# Principal.net
KiCad netlist of a schematic drawn in Altium Designer
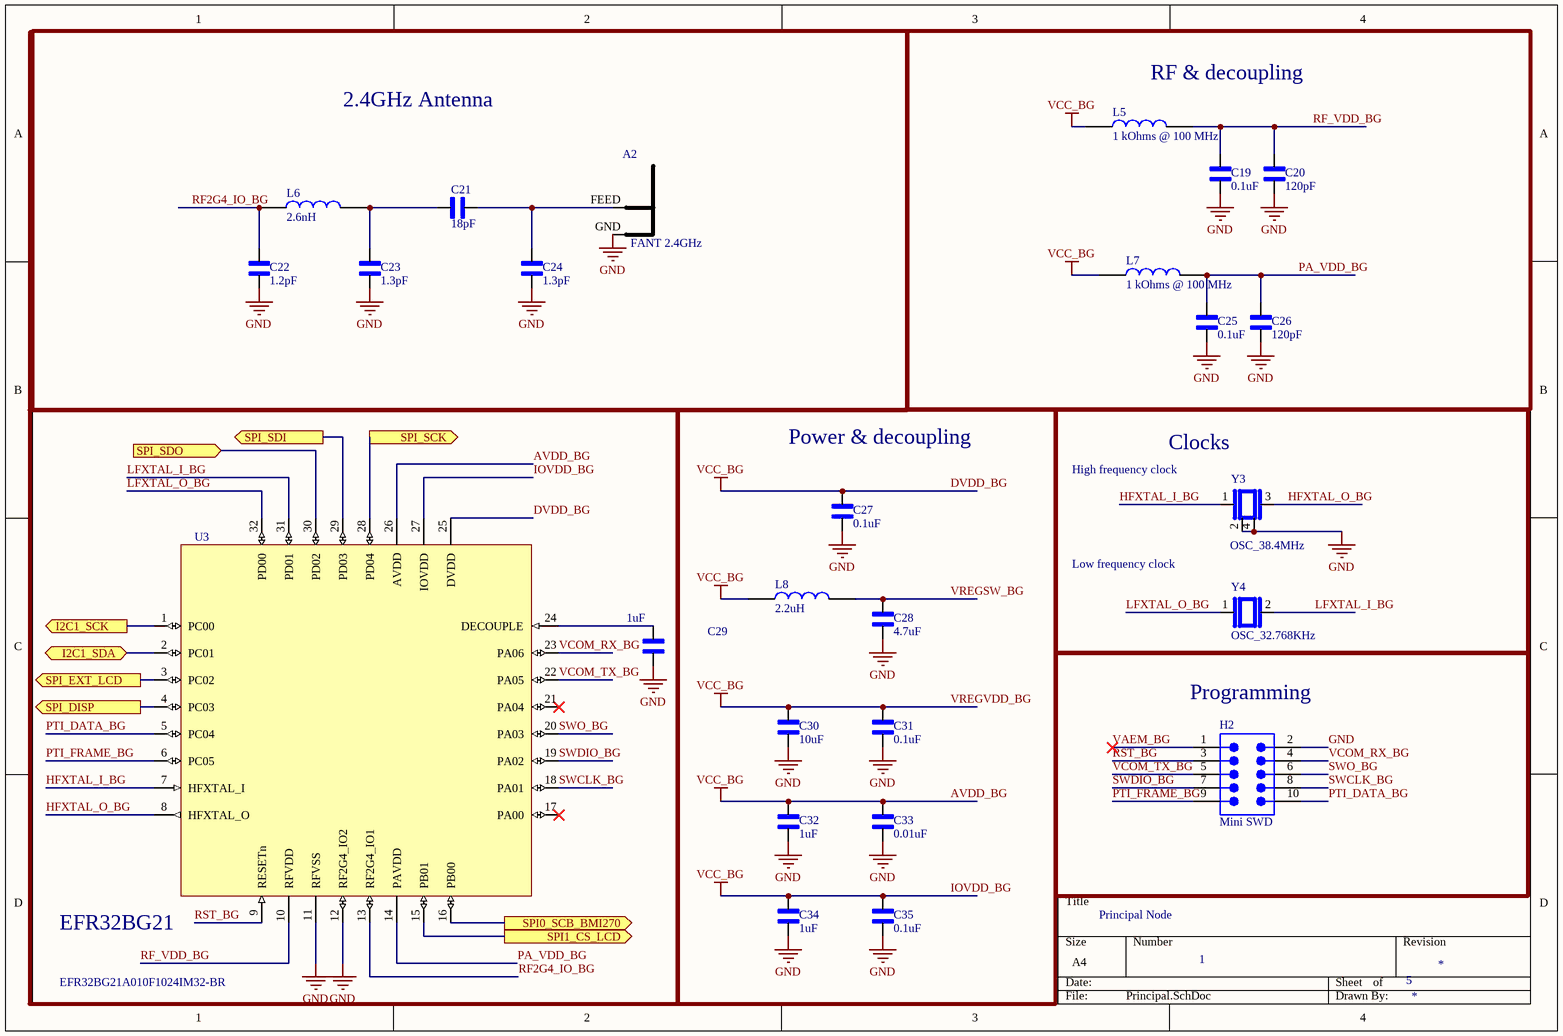
[diagram p0: Principal.SchDoc]

(export (version "E")
  (design (tool "Eeschema 10.0.6"))
  (components
    (comp (ref "A2")
      (value "FANT 2.4GHz")
      (footprint "FANT_2P4")
      (description "Inverted F antenna")
      (libsource (lib "Project_Vega") (part "FANT_2P4"))
    )
    (comp (ref "C19")
      (value "0.1uF")
      (footprint "CAPC1608X90")
      (description "0.1 ÂµF Â±10% 50V Ceramic Capacitor X7R 0603 (1608 Metric)")
      (fields (field (name "MF") "Yageo") (field (name "MP") "CC0603KRX7R9BB104"))
      (libsource (lib "Project_Vega") (part "CC0603KRX7R9BB104"))
    )
    (comp (ref "C20")
      (value "120pF")
      (footprint "CAPC1608X90")
      (description "0.1 ÂµF Â±10% 50V Ceramic Capacitor X7R 0603 (1608 Metric)")
      (fields (field (name "MF") "Yageo") (field (name "MP") "CC0603KRX7R9BB104"))
      (libsource (lib "Project_Vega") (part "CC0603KRX7R9BB104"))
    )
    (comp (ref "C21")
      (value "18pF")
      (footprint "CAPC1608X90")
      (description "0.1 ÂµF Â±10% 50V Ceramic Capacitor X7R 0603 (1608 Metric)")
      (fields (field (name "MF") "Yageo") (field (name "MP") "CC0603KRX7R9BB104"))
      (libsource (lib "") (part "CC0603KRX7R9BB104_1"))
    )
    (comp (ref "C22")
      (value "1.2pF")
      (footprint "CAPC1608X90")
      (description "0.1 ÂµF Â±10% 50V Ceramic Capacitor X7R 0603 (1608 Metric)")
      (fields (field (name "MF") "Yageo") (field (name "MP") "CC0603KRX7R9BB104"))
      (libsource (lib "Project_Vega") (part "CC0603KRX7R9BB104"))
    )
    (comp (ref "C23")
      (value "1.3pF")
      (footprint "CAPC1608X90")
      (description "0.1 ÂµF Â±10% 50V Ceramic Capacitor X7R 0603 (1608 Metric)")
      (fields (field (name "MF") "Yageo") (field (name "MP") "CC0603KRX7R9BB104"))
      (libsource (lib "Project_Vega") (part "CC0603KRX7R9BB104"))
    )
    (comp (ref "C24")
      (value "1.3pF")
      (footprint "CAPC1608X90")
      (description "0.1 ÂµF Â±10% 50V Ceramic Capacitor X7R 0603 (1608 Metric)")
      (fields (field (name "MF") "Yageo") (field (name "MP") "CC0603KRX7R9BB104"))
      (libsource (lib "Project_Vega") (part "CC0603KRX7R9BB104"))
    )
    (comp (ref "C25")
      (value "0.1uF")
      (footprint "CAPC1608X90")
      (description "0.1 ÂµF Â±10% 50V Ceramic Capacitor X7R 0603 (1608 Metric)")
      (fields (field (name "MF") "Yageo") (field (name "MP") "CC0603KRX7R9BB104"))
      (libsource (lib "Project_Vega") (part "CC0603KRX7R9BB104"))
    )
    (comp (ref "C26")
      (value "120pF")
      (footprint "CAPC1608X90")
      (description "0.1 ÂµF Â±10% 50V Ceramic Capacitor X7R 0603 (1608 Metric)")
      (fields (field (name "MF") "Yageo") (field (name "MP") "CC0603KRX7R9BB104"))
      (libsource (lib "Project_Vega") (part "CC0603KRX7R9BB104"))
    )
    (comp (ref "C27")
      (value "0.1uF")
      (footprint "CAPC1608X90")
      (description "0.1 ÂµF Â±10% 50V Ceramic Capacitor X7R 0603 (1608 Metric)")
      (fields (field (name "MF") "Yageo") (field (name "MP") "CC0603KRX7R9BB104"))
      (libsource (lib "Project_Vega") (part "CC0603KRX7R9BB104"))
    )
    (comp (ref "C28")
      (value "4.7uF")
      (footprint "CAPC1608X90")
      (description "0.1 ÂµF Â±10% 50V Ceramic Capacitor X7R 0603 (1608 Metric)")
      (fields (field (name "MF") "Yageo") (field (name "MP") "CC0603KRX7R9BB104"))
      (libsource (lib "Project_Vega") (part "CC0603KRX7R9BB104"))
    )
    (comp (ref "C29")
      (value "1uF")
      (footprint "CAPC1608X90")
      (description "0.1 ÂµF Â±10% 50V Ceramic Capacitor X7R 0603 (1608 Metric)")
      (fields (field (name "MF") "Yageo") (field (name "MP") "CC0603KRX7R9BB104"))
      (libsource (lib "Project_Vega") (part "CC0603KRX7R9BB104"))
    )
    (comp (ref "C30")
      (value "10uF")
      (footprint "CAPC1608X90")
      (description "0.1 ÂµF Â±10% 50V Ceramic Capacitor X7R 0603 (1608 Metric)")
      (fields (field (name "MF") "Yageo") (field (name "MP") "CC0603KRX7R9BB104"))
      (libsource (lib "Project_Vega") (part "CC0603KRX7R9BB104"))
    )
    (comp (ref "C31")
      (value "0.1uF")
      (footprint "CAPC1608X90")
      (description "0.1 ÂµF Â±10% 50V Ceramic Capacitor X7R 0603 (1608 Metric)")
      (fields (field (name "MF") "Yageo") (field (name "MP") "CC0603KRX7R9BB104"))
      (libsource (lib "Project_Vega") (part "CC0603KRX7R9BB104"))
    )
    (comp (ref "C32")
      (value "1uF")
      (footprint "CAPC1608X90")
      (description "0.1 ÂµF Â±10% 50V Ceramic Capacitor X7R 0603 (1608 Metric)")
      (fields (field (name "MF") "Yageo") (field (name "MP") "CC0603KRX7R9BB104"))
      (libsource (lib "Project_Vega") (part "CC0603KRX7R9BB104"))
    )
    (comp (ref "C33")
      (value "0.01uF")
      (footprint "CAPC1608X90")
      (description "0.1 ÂµF Â±10% 50V Ceramic Capacitor X7R 0603 (1608 Metric)")
      (fields (field (name "MF") "Yageo") (field (name "MP") "CC0603KRX7R9BB104"))
      (libsource (lib "Project_Vega") (part "CC0603KRX7R9BB104"))
    )
    (comp (ref "C34")
      (value "1uF")
      (footprint "CAPC1608X90")
      (description "0.1 ÂµF Â±10% 50V Ceramic Capacitor X7R 0603 (1608 Metric)")
      (fields (field (name "MF") "Yageo") (field (name "MP") "CC0603KRX7R9BB104"))
      (libsource (lib "Project_Vega") (part "CC0603KRX7R9BB104"))
    )
    (comp (ref "C35")
      (value "0.1uF")
      (footprint "CAPC1608X90")
      (description "0.1 ÂµF Â±10% 50V Ceramic Capacitor X7R 0603 (1608 Metric)")
      (fields (field (name "MF") "Yageo") (field (name "MP") "CC0603KRX7R9BB104"))
      (libsource (lib "Project_Vega") (part "CC0603KRX7R9BB104"))
    )
    (comp (ref "H2")
      (value "Mini SWD")
      (footprint "FTSH-105-01-XXX-DV-K")
      (description "Mini SWD 0.05\" Pitch Connector - 10 Pin SMT Box Header")
      (fields
        (field (name "MANUFACTURER") "Adafruit Industries")
        (field (name "MANUFACTURER PART NUMBER") "4048")
      )
      (libsource (lib "Connectors") (part "Debug Connector Mini SWD - 0.05{dblquote}"))
    )
    (comp (ref "L5")
      (value "1 kOhms @ 100 MHz")
      (footprint "INDC1608X95N")
      (description "Inductor with Inductance 10uH Tol.+/-20% Package 0603 (1608)")
      (fields (field (name "MP") "LQM18DN100M70L") (field (name "MF") "Murata Electronics"))
      (libsource (lib "Project_Vega") (part "LQM18DN100M70L"))
    )
    (comp (ref "L6")
      (value "2.6nH")
      (footprint "INDC1608X95N")
      (description "Inductor with Inductance 10uH Tol.+/-20% Package 0603 (1608)")
      (fields (field (name "MP") "LQM18DN100M70L") (field (name "MF") "Murata Electronics"))
      (libsource (lib "Project_Vega") (part "LQM18DN100M70L"))
    )
    (comp (ref "L7")
      (value "1 kOhms @ 100 MHz")
      (footprint "INDC1608X95N")
      (description "Inductor with Inductance 10uH Tol.+/-20% Package 0603 (1608)")
      (fields (field (name "MP") "LQM18DN100M70L") (field (name "MF") "Murata Electronics"))
      (libsource (lib "Project_Vega") (part "LQM18DN100M70L"))
    )
    (comp (ref "L8")
      (value "2.2uH")
      (footprint "INDC1608X95N")
      (description "Inductor with Inductance 10uH Tol.+/-20% Package 0603 (1608)")
      (fields (field (name "MP") "LQM18DN100M70L") (field (name "MF") "Murata Electronics"))
      (libsource (lib "Project_Vega") (part "LQM18DN100M70L"))
    )
    (comp (ref "U3")
      (value "EFR32BG21A010F1024IM32-BR")
      (footprint "QFN32-EFR32xG2xIM32-BR")
      (description "Blue Gecko, QFN32, 2.4G, 10dB, Bluetooth 5.1, 1024kB, 96kB(RAM), 20 GPIO")
      (fields (field (name "MANUFACTURER") "Silicon Labs"))
      (libsource (lib "Project_Vega") (part "EFR32BG21A010F1024IM32-BR"))
    )
    (comp (ref "Y3")
      (value "OSC_38.4MHz")
      (footprint "OSC_38.4MHz")
      (description "38.4 MHz ±10ppm Crystal 10pF 40 Ohms 4-SMD, No Lead")
      (fields
        (field (name "MF") "{'manufacturer': u'Murata Electronics'}")
        (field (name "MP") "XRCGB38M400F2P00R0")
      )
      (libsource (lib "Project_Vega") (part "OSC_38.4MHz"))
    )
    (comp (ref "Y4")
      (value "OSC_32.768KHz")
      (footprint "OSC_32.768KHz")
      (description "Tuning Fork Crystal 32.768kHz in 1.2 x 2.0mm package")
      (fields (field (name "MF") "Micro Crystal") (field (name "MP") "CM8V-T1A-32.768KHZ-7PF-20PPM-TA-QC"))
      (libsource (lib "Project_Vega") (part "OSC_32.768KHz"))
    )
  )
  (nets
    (net (code "1") (name "/HFXTAL_I_BG") (class "Default")
      (node (ref "U3") (pin "7") (pinfunction "HFXTAL_I_7") (pintype "input"))
      (node (ref "Y3") (pin "1") (pinfunction "1_1") (pintype "passive"))
    )
    (net (code "2") (name "/HFXTAL_O_BG") (class "Default")
      (node (ref "U3") (pin "8") (pinfunction "HFXTAL_O_8") (pintype "output"))
      (node (ref "Y3") (pin "3") (pinfunction "3_3") (pintype "passive"))
    )
    (net (code "3") (name "/I2C1_SCK") (class "Default")
      (node (ref "U3") (pin "1") (pinfunction "PC00_1") (pintype "bidirectional"))
    )
    (net (code "4") (name "/I2C1_SDA") (class "Default")
      (node (ref "U3") (pin "2") (pinfunction "PC01_2") (pintype "bidirectional"))
    )
    (net (code "5") (name "/LFXTAL_I_BG") (class "Default")
      (node (ref "U3") (pin "31") (pinfunction "PD01_31") (pintype "bidirectional"))
      (node (ref "Y4") (pin "2") (pinfunction "2_2") (pintype "passive"))
    )
    (net (code "6") (name "/LFXTAL_O_BG") (class "Default")
      (node (ref "U3") (pin "32") (pinfunction "PD00_32") (pintype "bidirectional"))
      (node (ref "Y4") (pin "1") (pinfunction "1_1") (pintype "passive"))
    )
    (net (code "7") (name "/PA_VDD_BG") (class "Default")
      (node (ref "C25") (pin "1") (pinfunction "1_1") (pintype "passive"))
      (node (ref "C26") (pin "1") (pinfunction "1_1") (pintype "passive"))
      (node (ref "L7") (pin "2") (pinfunction "2_2") (pintype "passive"))
      (node (ref "U3") (pin "14") (pinfunction "PAVDD_14") (pintype "power_in"))
    )
    (net (code "8") (name "/PTI_DATA_BG") (class "Default")
      (node (ref "H2") (pin "10") (pinfunction "10_10") (pintype "passive"))
      (node (ref "U3") (pin "5") (pinfunction "PC04_5") (pintype "bidirectional"))
    )
    (net (code "9") (name "/PTI_FRAME_BG") (class "Default")
      (node (ref "H2") (pin "9") (pinfunction "9_9") (pintype "passive"))
      (node (ref "U3") (pin "6") (pinfunction "PC05_6") (pintype "bidirectional"))
    )
    (net (code "10") (name "/RF2G4_IO_BG") (class "Default")
      (node (ref "C22") (pin "1") (pinfunction "1_1") (pintype "passive"))
      (node (ref "L6") (pin "1") (pinfunction "1_1") (pintype "passive"))
      (node (ref "U3") (pin "13") (pinfunction "RF2G4_IO1_13") (pintype "bidirectional"))
    )
    (net (code "11") (name "/RF_VDD_BG") (class "Default")
      (node (ref "C19") (pin "1") (pinfunction "1_1") (pintype "passive"))
      (node (ref "C20") (pin "1") (pinfunction "1_1") (pintype "passive"))
      (node (ref "L5") (pin "2") (pinfunction "2_2") (pintype "passive"))
      (node (ref "U3") (pin "10") (pinfunction "RFVDD_10") (pintype "power_in"))
    )
    (net (code "12") (name "/RST_BG") (class "Default")
      (node (ref "H2") (pin "3") (pinfunction "3_3") (pintype "passive"))
      (node (ref "U3") (pin "9") (pinfunction "RESETn_9") (pintype "input"))
    )
    (net (code "13") (name "/SPI0_SCB_BMI270") (class "Default")
      (node (ref "U3") (pin "16") (pinfunction "PB00_16") (pintype "bidirectional"))
    )
    (net (code "14") (name "/SPI1_CS_LCD") (class "Default")
      (node (ref "U3") (pin "15") (pinfunction "PB01_15") (pintype "bidirectional"))
    )
    (net (code "15") (name "/SPI_DISP") (class "Default")
      (node (ref "U3") (pin "4") (pinfunction "PC03_4") (pintype "bidirectional"))
    )
    (net (code "16") (name "/SPI_EXT_LCD") (class "Default")
      (node (ref "U3") (pin "3") (pinfunction "PC02_3") (pintype "bidirectional"))
    )
    (net (code "17") (name "/SPI_SCK") (class "Default")
      (node (ref "U3") (pin "28") (pinfunction "PD04_28") (pintype "bidirectional"))
    )
    (net (code "18") (name "/SPI_SDI") (class "Default")
      (node (ref "U3") (pin "29") (pinfunction "PD03_29") (pintype "bidirectional"))
    )
    (net (code "19") (name "/SPI_SDO") (class "Default")
      (node (ref "U3") (pin "30") (pinfunction "PD02_30") (pintype "bidirectional"))
    )
    (net (code "20") (name "/SWCLK_BG") (class "Default")
      (node (ref "H2") (pin "8") (pinfunction "8_8") (pintype "passive"))
      (node (ref "U3") (pin "18") (pinfunction "PA01_18") (pintype "bidirectional"))
    )
    (net (code "21") (name "/SWDIO_BG") (class "Default")
      (node (ref "H2") (pin "7") (pinfunction "7_7") (pintype "passive"))
      (node (ref "U3") (pin "19") (pinfunction "PA02_19") (pintype "bidirectional"))
    )
    (net (code "22") (name "/SWO_BG") (class "Default")
      (node (ref "H2") (pin "6") (pinfunction "6_6") (pintype "passive"))
      (node (ref "U3") (pin "20") (pinfunction "PA03_20") (pintype "bidirectional"))
    )
    (net (code "23") (name "/VAEM_BG") (class "Default")
      (node (ref "H2") (pin "1") (pinfunction "1_1") (pintype "passive+no_connect"))
    )
    (net (code "24") (name "/VCOM_RX_BG") (class "Default")
      (node (ref "H2") (pin "4") (pinfunction "4_4") (pintype "passive"))
      (node (ref "U3") (pin "23") (pinfunction "PA06_23") (pintype "bidirectional"))
    )
    (net (code "25") (name "/VCOM_TX_BG") (class "Default")
      (node (ref "H2") (pin "5") (pinfunction "5_5") (pintype "passive"))
      (node (ref "U3") (pin "22") (pinfunction "PA05_22") (pintype "bidirectional"))
    )
    (net (code "26") (name "/VREGSW_BG") (class "Default")
      (node (ref "C28") (pin "1") (pinfunction "1_1") (pintype "passive"))
      (node (ref "L8") (pin "2") (pinfunction "2_2") (pintype "passive"))
    )
    (net (code "27") (name "GND") (class "Default")
      (node (ref "A2") (pin "GND") (pinfunction "6_GND") (pintype "passive"))
      (node (ref "C19") (pin "2") (pinfunction "2_2") (pintype "passive"))
      (node (ref "C20") (pin "2") (pinfunction "2_2") (pintype "passive"))
      (node (ref "C22") (pin "2") (pinfunction "2_2") (pintype "passive"))
      (node (ref "C23") (pin "2") (pinfunction "2_2") (pintype "passive"))
      (node (ref "C24") (pin "2") (pinfunction "2_2") (pintype "passive"))
      (node (ref "C25") (pin "2") (pinfunction "2_2") (pintype "passive"))
      (node (ref "C26") (pin "2") (pinfunction "2_2") (pintype "passive"))
      (node (ref "C27") (pin "2") (pinfunction "2_2") (pintype "passive"))
      (node (ref "C28") (pin "2") (pinfunction "2_2") (pintype "passive"))
      (node (ref "C29") (pin "2") (pinfunction "2_2") (pintype "passive"))
      (node (ref "C30") (pin "2") (pinfunction "2_2") (pintype "passive"))
      (node (ref "C31") (pin "2") (pinfunction "2_2") (pintype "passive"))
      (node (ref "C32") (pin "2") (pinfunction "2_2") (pintype "passive"))
      (node (ref "C33") (pin "2") (pinfunction "2_2") (pintype "passive"))
      (node (ref "C34") (pin "2") (pinfunction "2_2") (pintype "passive"))
      (node (ref "C35") (pin "2") (pinfunction "2_2") (pintype "passive"))
      (node (ref "H2") (pin "2") (pinfunction "2_2") (pintype "passive"))
      (node (ref "U3") (pin "11") (pinfunction "RFVSS_11") (pintype "power_in"))
      (node (ref "U3") (pin "12") (pinfunction "RF2G4_IO2_12") (pintype "bidirectional"))
      (node (ref "Y3") (pin "2") (pinfunction "2_2") (pintype "passive"))
      (node (ref "Y3") (pin "4") (pinfunction "4_4") (pintype "passive"))
    )
    (net (code "28") (name "Net-(A2-6-PadFEED)") (class "Default")
      (node (ref "A2") (pin "FEED") (pinfunction "6_FEED") (pintype "passive"))
      (node (ref "C21") (pin "2") (pinfunction "2_2") (pintype "passive"))
      (node (ref "C24") (pin "1") (pinfunction "1_1") (pintype "passive"))
    )
    (net (code "29") (name "Net-(C21-Pad1)") (class "Default")
      (node (ref "C21") (pin "1") (pinfunction "1_1") (pintype "passive"))
      (node (ref "C23") (pin "1") (pinfunction "1_1") (pintype "passive"))
      (node (ref "L6") (pin "2") (pinfunction "2_2") (pintype "passive"))
    )
    (net (code "30") (name "Net-(U3-DECOUPLE)") (class "Default")
      (node (ref "C29") (pin "1") (pinfunction "1_1") (pintype "passive"))
      (node (ref "U3") (pin "24") (pinfunction "DECOUPLE_24") (pintype "input"))
    )
    (net (code "31") (name "VCC_BG") (class "Default")
      (node (ref "C27") (pin "1") (pinfunction "1_1") (pintype "passive"))
      (node (ref "C30") (pin "1") (pinfunction "1_1") (pintype "passive"))
      (node (ref "C31") (pin "1") (pinfunction "1_1") (pintype "passive"))
      (node (ref "C32") (pin "1") (pinfunction "1_1") (pintype "passive"))
      (node (ref "C33") (pin "1") (pinfunction "1_1") (pintype "passive"))
      (node (ref "C34") (pin "1") (pinfunction "1_1") (pintype "passive"))
      (node (ref "C35") (pin "1") (pinfunction "1_1") (pintype "passive"))
      (node (ref "L5") (pin "1") (pinfunction "1_1") (pintype "passive"))
      (node (ref "L7") (pin "1") (pinfunction "1_1") (pintype "passive"))
      (node (ref "L8") (pin "1") (pinfunction "1_1") (pintype "passive"))
      (node (ref "U3") (pin "25") (pinfunction "DVDD_25") (pintype "power_in"))
      (node (ref "U3") (pin "26") (pinfunction "AVDD_26") (pintype "power_in"))
      (node (ref "U3") (pin "27") (pinfunction "IOVDD_27") (pintype "power_in"))
    )
    (net (code "32") (name "unconnected-(U3-PA00-Pad17)") (class "Default")
      (node (ref "U3") (pin "17") (pinfunction "PA00_17") (pintype "bidirectional+no_connect"))
    )
    (net (code "33") (name "unconnected-(U3-PA04-Pad21)") (class "Default")
      (node (ref "U3") (pin "21") (pinfunction "PA04_21") (pintype "bidirectional+no_connect"))
    )
  )
)
